# sensor_v5.net
KiCad netlist of a schematic drawn in EAGLE
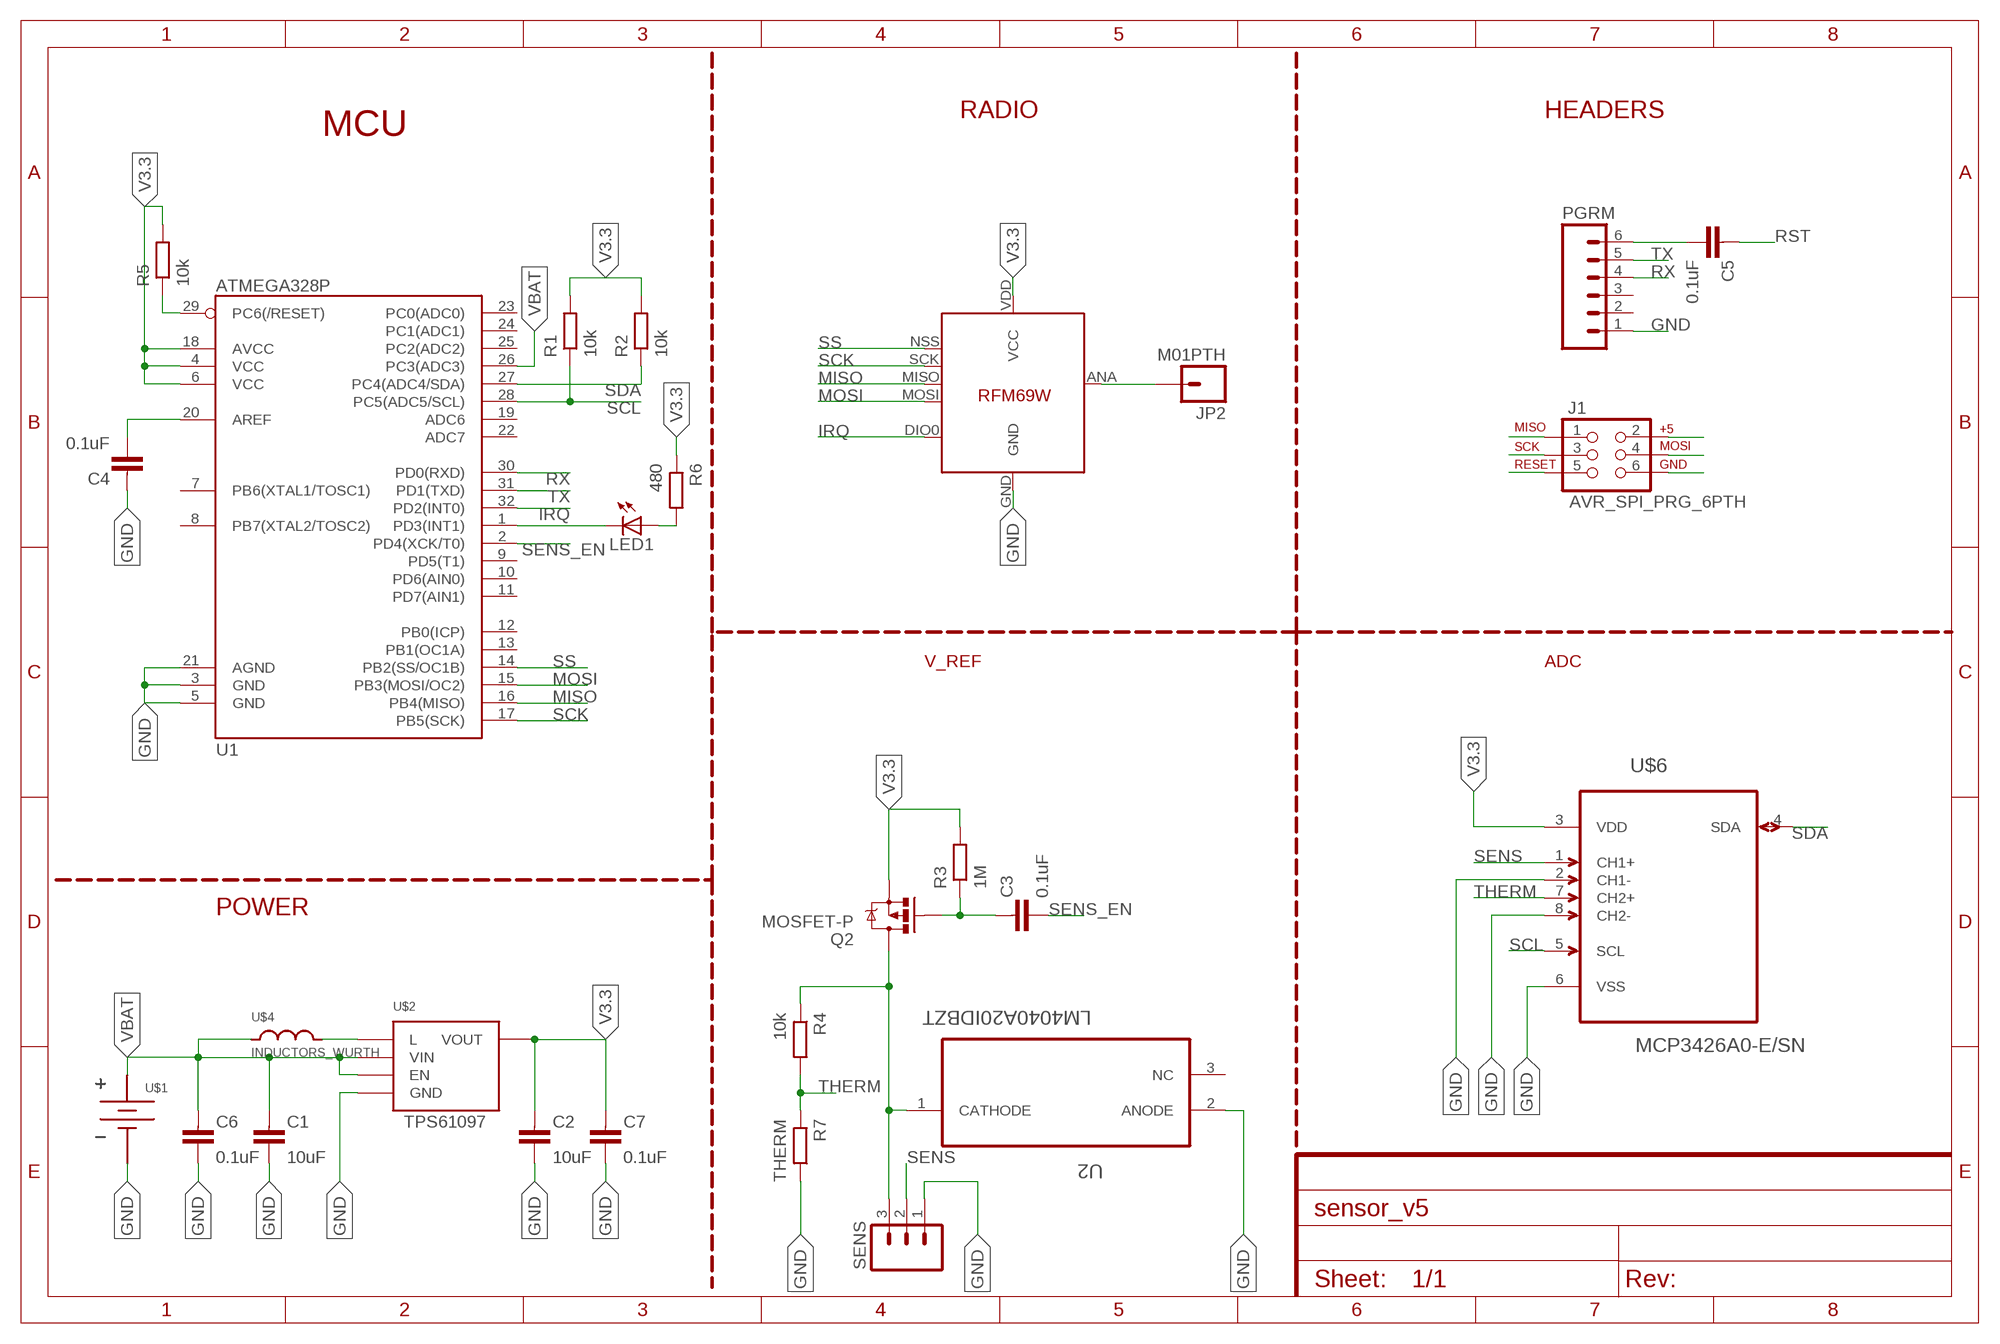
[diagram p0: schematic, sheet 1]

(export (version "E")
  (design (tool "Eeschema 10.0.6"))
  (components
    (comp (ref "C1")
      (value "10uF")
      (footprint "eagle-import:C0805-N")
      (libsource (lib "eagle-import") (part "CAPACITOR0805-N"))
    )
    (comp (ref "C2")
      (value "10uF")
      (footprint "eagle-import:C0805-N")
      (libsource (lib "eagle-import") (part "CAPACITOR0805-N"))
    )
    (comp (ref "C3")
      (value "0.1uF")
      (footprint "eagle-import:C0603-N")
      (libsource (lib "eagle-import") (part "CAPACITOR0603-N"))
    )
    (comp (ref "C4")
      (value "0.1uF")
      (footprint "eagle-import:C0603-N")
      (libsource (lib "eagle-import") (part "CAPACITOR0603-N"))
    )
    (comp (ref "C5")
      (value "0.1uF")
      (footprint "eagle-import:C0603-N")
      (libsource (lib "eagle-import") (part "CAPACITOR0603-N"))
    )
    (comp (ref "C6")
      (value "0.1uF")
      (footprint "eagle-import:C0603-N")
      (libsource (lib "eagle-import") (part "CAPACITOR0603-N"))
    )
    (comp (ref "C7")
      (value "0.1uF")
      (footprint "eagle-import:C0603-N")
      (libsource (lib "eagle-import") (part "CAPACITOR0603-N"))
    )
    (comp (ref "J1")
      (value "AVR_SPI_PRG_6PTH")
      (footprint "eagle-import:2X3")
      (libsource (lib "eagle-import") (part "AVR_SPI_PRG_6PTH"))
    )
    (comp (ref "JP2")
      (value "M01PTH")
      (footprint "eagle-import:1X01")
      (libsource (lib "eagle-import") (part "M01PTH"))
    )
    (comp (ref "LED1")
      (value "LED0603")
      (footprint "eagle-import:LED-0603")
      (libsource (lib "eagle-import") (part "LED0603"))
    )
    (comp (ref "PGRM")
      (value "M06LONGPADS")
      (footprint "eagle-import:1X06_LONGPADS")
      (libsource (lib "eagle-import") (part "M06LONGPADS"))
    )
    (comp (ref "Q2")
      (value "MOSFET-P")
      (footprint "eagle-import:SOT23-3")
      (libsource (lib "eagle-import") (part "MOSFET-PCHANNELIRLML2244"))
    )
    (comp (ref "R1")
      (value "10k")
      (footprint "eagle-import:R0603-N")
      (libsource (lib "eagle-import") (part "RESISTOR0603-N"))
    )
    (comp (ref "R2")
      (value "10k")
      (footprint "eagle-import:R0603-N")
      (libsource (lib "eagle-import") (part "RESISTOR0603-N"))
    )
    (comp (ref "R3")
      (value "1M")
      (footprint "eagle-import:R0603-N")
      (libsource (lib "eagle-import") (part "RESISTOR0603-N"))
    )
    (comp (ref "R4")
      (value "10k")
      (footprint "eagle-import:R0603-N")
      (libsource (lib "eagle-import") (part "RESISTOR0603-N"))
    )
    (comp (ref "R5")
      (value "10k")
      (footprint "eagle-import:R0603-N")
      (libsource (lib "eagle-import") (part "RESISTOR0603-N"))
    )
    (comp (ref "R6")
      (value "480")
      (footprint "eagle-import:R0603-N")
      (libsource (lib "eagle-import") (part "RESISTOR0603-N"))
    )
    (comp (ref "R7")
      (value "THERM")
      (footprint "eagle-import:R0603-N")
      (libsource (lib "eagle-import") (part "RESISTOR0603-N"))
    )
    (comp (ref "SENS")
      (value "M03PTH")
      (footprint "eagle-import:1X03")
      (libsource (lib "eagle-import") (part "M03PTH"))
    )
    (comp (ref "U$1")
      (value "KEYSTONEAAHOLDER_2CELL")
      (footprint "eagle-import:KEYSTONEAAHOLDER_2CELL")
      (libsource (lib "eagle-import") (part "KEYSTONEAAHOLDER_2CELL"))
    )
    (comp (ref "U$2")
      (value "TPS61097-33")
      (footprint "eagle-import:SOT23-5")
      (libsource (lib "eagle-import") (part "TPS61097-33"))
    )
    (comp (ref "U$4")
      (value "INDUCTORS_WURTH")
      (footprint "eagle-import:WURTH_10UH_650MA")
      (libsource (lib "eagle-import") (part "INDUCTORS_WURTH"))
    )
    (comp (ref "U$5")
      (value "RFM69")
      (footprint "eagle-import:RFM69W-MINPADS")
      (libsource (lib "eagle-import") (part "RFM69"))
    )
    (comp (ref "U$6")
      (value "MCP3426A0-E/SN")
      (footprint "eagle-import:SOIC127P600X175-8N")
      (libsource (lib "eagle-import") (part "MCP3426A0-E/SN"))
    )
    (comp (ref "U1")
      (value "ATMEGA328P")
      (footprint "eagle-import:TQFP32-08")
      (libsource (lib "eagle-import") (part "ATMEGA328_SMT"))
    )
    (comp (ref "U2")
      (value "LM4040A20IDBZT")
      (footprint "eagle-import:SOT95P237X112-3N")
      (libsource (lib "eagle-import") (part "LM4040A20IDBZT"))
    )
  )
  (nets
    (net (code "1") (name "/IRQ") (class "Default")
      (node (ref "U$5") (pin "DIO0") (pinfunction "DIO0_DIO0") (pintype "open_collector"))
      (node (ref "U1") (pin "32") (pinfunction "PD2(INT0)_32") (pintype "bidirectional"))
    )
    (net (code "2") (name "/MISO") (class "Default")
      (node (ref "J1") (pin "1") (pinfunction "1_1") (pintype "passive"))
      (node (ref "U$5") (pin "MISO") (pinfunction "MISO_MISO") (pintype "input"))
      (node (ref "U1") (pin "16") (pinfunction "PB4(MISO)_16") (pintype "bidirectional"))
    )
    (net (code "3") (name "/MOSI") (class "Default")
      (node (ref "J1") (pin "4") (pinfunction "4_4") (pintype "passive"))
      (node (ref "U$5") (pin "MOSI") (pinfunction "MOSI_MOSI") (pintype "output"))
      (node (ref "U1") (pin "15") (pinfunction "PB3(MOSI/OC2)_15") (pintype "bidirectional"))
    )
    (net (code "4") (name "/RST") (class "Default")
      (node (ref "C5") (pin "1") (pinfunction "1_1") (pintype "passive"))
      (node (ref "J1") (pin "5") (pinfunction "5_5") (pintype "passive"))
      (node (ref "R5") (pin "1") (pinfunction "P$1_1") (pintype "passive"))
      (node (ref "U1") (pin "29") (pinfunction "PC6(/RESET)_29") (pintype "bidirectional"))
    )
    (net (code "5") (name "/RX") (class "Default")
      (node (ref "PGRM") (pin "4") (pinfunction "4_4") (pintype "passive"))
      (node (ref "U1") (pin "30") (pinfunction "PD0(RXD)_30") (pintype "bidirectional"))
    )
    (net (code "6") (name "/SCK") (class "Default")
      (node (ref "J1") (pin "3") (pinfunction "3_3") (pintype "passive"))
      (node (ref "U$5") (pin "SCK") (pinfunction "SCK_SCK") (pintype "input"))
      (node (ref "U1") (pin "17") (pinfunction "PB5(SCK)_17") (pintype "bidirectional"))
    )
    (net (code "7") (name "/SCL") (class "Default")
      (node (ref "R1") (pin "1") (pinfunction "P$1_1") (pintype "passive"))
      (node (ref "U$6") (pin "5") (pinfunction "SCL_5") (pintype "input"))
      (node (ref "U1") (pin "28") (pinfunction "PC5(ADC5/SCL)_28") (pintype "bidirectional"))
    )
    (net (code "8") (name "/SDA") (class "Default")
      (node (ref "R2") (pin "1") (pinfunction "P$1_1") (pintype "passive"))
      (node (ref "U$6") (pin "4") (pinfunction "SDA_4") (pintype "bidirectional"))
      (node (ref "U1") (pin "27") (pinfunction "PC4(ADC4/SDA)_27") (pintype "bidirectional"))
    )
    (net (code "9") (name "/SENS") (class "Default")
      (node (ref "SENS") (pin "2") (pinfunction "2_2") (pintype "passive"))
      (node (ref "U$6") (pin "1") (pinfunction "CH1+_1") (pintype "input"))
    )
    (net (code "10") (name "/SENS_EN") (class "Default")
      (node (ref "C3") (pin "2") (pinfunction "2_2") (pintype "passive"))
      (node (ref "U1") (pin "2") (pinfunction "PD4(XCK/T0)_2") (pintype "bidirectional"))
    )
    (net (code "11") (name "/SS") (class "Default")
      (node (ref "U$5") (pin "NSS") (pinfunction "SEL_NSS") (pintype "input"))
      (node (ref "U1") (pin "14") (pinfunction "PB2(SS/OC1B)_14") (pintype "bidirectional"))
    )
    (net (code "12") (name "/THERM") (class "Default")
      (node (ref "R4") (pin "2") (pinfunction "P$2_2") (pintype "passive"))
      (node (ref "R7") (pin "1") (pinfunction "P$1_1") (pintype "passive"))
      (node (ref "U$6") (pin "7") (pinfunction "CH2+_7") (pintype "input"))
    )
    (net (code "13") (name "/TX") (class "Default")
      (node (ref "PGRM") (pin "5") (pinfunction "5_5") (pintype "passive"))
      (node (ref "U1") (pin "31") (pinfunction "PD1(TXD)_31") (pintype "bidirectional"))
    )
    (net (code "14") (name "GND") (class "Default")
      (node (ref "C1") (pin "2") (pinfunction "2_2") (pintype "passive"))
      (node (ref "C2") (pin "2") (pinfunction "2_2") (pintype "passive"))
      (node (ref "C4") (pin "1") (pinfunction "1_1") (pintype "passive"))
      (node (ref "C6") (pin "2") (pinfunction "2_2") (pintype "passive"))
      (node (ref "C7") (pin "2") (pinfunction "2_2") (pintype "passive"))
      (node (ref "J1") (pin "6") (pinfunction "6_6") (pintype "passive"))
      (node (ref "PGRM") (pin "1") (pinfunction "1_1") (pintype "passive"))
      (node (ref "R7") (pin "2") (pinfunction "P$2_2") (pintype "passive"))
      (node (ref "SENS") (pin "1") (pinfunction "1_1") (pintype "passive"))
      (node (ref "U$1") (pin "P$2") (pinfunction "GND_P$2") (pintype "bidirectional"))
      (node (ref "U$2") (pin "P$2") (pinfunction "GND_P$2") (pintype "power_in"))
      (node (ref "U$5") (pin "GND") (pinfunction "GND_GND") (pintype "power_in"))
      (node (ref "U$6") (pin "2") (pinfunction "CH1-_2") (pintype "input"))
      (node (ref "U$6") (pin "6") (pinfunction "VSS_6") (pintype "power_in"))
      (node (ref "U$6") (pin "8") (pinfunction "CH2-_8") (pintype "input"))
      (node (ref "U1") (pin "21") (pinfunction "AGND_21") (pintype "bidirectional"))
      (node (ref "U1") (pin "3") (pinfunction "GND_3") (pintype "bidirectional"))
      (node (ref "U1") (pin "5") (pinfunction "GND_5") (pintype "bidirectional"))
      (node (ref "U2") (pin "2") (pinfunction "ANODE_2") (pintype "input"))
    )
    (net (code "15") (name "Net-(C5-Pad2)") (class "Default")
      (node (ref "C5") (pin "2") (pinfunction "2_2") (pintype "passive"))
      (node (ref "PGRM") (pin "6") (pinfunction "6_6") (pintype "passive"))
    )
    (net (code "16") (name "Net-(Q2-D)") (class "Default")
      (node (ref "Q2") (pin "3") (pinfunction "D_3") (pintype "passive"))
      (node (ref "R4") (pin "1") (pinfunction "P$1_1") (pintype "passive"))
      (node (ref "SENS") (pin "3") (pinfunction "3_3") (pintype "passive"))
      (node (ref "U2") (pin "1") (pinfunction "CATHODE_1") (pintype "output"))
    )
    (net (code "17") (name "Net-(Q2-G)") (class "Default")
      (node (ref "C3") (pin "1") (pinfunction "1_1") (pintype "passive"))
      (node (ref "Q2") (pin "1") (pinfunction "G_1") (pintype "passive"))
      (node (ref "R3") (pin "1") (pinfunction "P$1_1") (pintype "passive"))
    )
    (net (code "18") (name "Net-(R6-P$2)") (class "Default")
      (node (ref "LED1") (pin "A") (pinfunction "A_A") (pintype "passive"))
      (node (ref "R6") (pin "2") (pinfunction "P$2_2") (pintype "passive"))
    )
    (net (code "19") (name "Net-(U$2-L)") (class "Default")
      (node (ref "U$2") (pin "P$5") (pinfunction "L_P$5") (pintype "bidirectional"))
      (node (ref "U$4") (pin "P$1") (pinfunction "P$1_P$1") (pintype "passive"))
    )
    (net (code "20") (name "Net-(U$5-ANT)") (class "Default")
      (node (ref "JP2") (pin "1") (pinfunction "1_1") (pintype "passive"))
      (node (ref "U$5") (pin "ANA") (pinfunction "ANT_ANA") (pintype "passive"))
    )
    (net (code "21") (name "Net-(U1-AREF)") (class "Default")
      (node (ref "C4") (pin "2") (pinfunction "2_2") (pintype "passive"))
      (node (ref "U1") (pin "20") (pinfunction "AREF_20") (pintype "bidirectional"))
    )
    (net (code "22") (name "Net-(U1-PD3(INT1))") (class "Default")
      (node (ref "LED1") (pin "C") (pinfunction "C_C") (pintype "passive"))
      (node (ref "U1") (pin "1") (pinfunction "PD3(INT1)_1") (pintype "bidirectional"))
    )
    (net (code "23") (name "V3.3") (class "Default")
      (node (ref "C2") (pin "1") (pinfunction "1_1") (pintype "passive"))
      (node (ref "C7") (pin "1") (pinfunction "1_1") (pintype "passive"))
      (node (ref "J1") (pin "2") (pinfunction "2_2") (pintype "passive"))
      (node (ref "Q2") (pin "2") (pinfunction "S_2") (pintype "passive"))
      (node (ref "R1") (pin "2") (pinfunction "P$2_2") (pintype "passive"))
      (node (ref "R2") (pin "2") (pinfunction "P$2_2") (pintype "passive"))
      (node (ref "R3") (pin "2") (pinfunction "P$2_2") (pintype "passive"))
      (node (ref "R5") (pin "2") (pinfunction "P$2_2") (pintype "passive"))
      (node (ref "R6") (pin "1") (pinfunction "P$1_1") (pintype "passive"))
      (node (ref "U$2") (pin "P$4") (pinfunction "VOUT_P$4") (pintype "power_in"))
      (node (ref "U$5") (pin "VDD") (pinfunction "VCC_VDD") (pintype "power_in"))
      (node (ref "U$6") (pin "3") (pinfunction "VDD_3") (pintype "power_in"))
      (node (ref "U1") (pin "18") (pinfunction "AVCC_18") (pintype "bidirectional"))
      (node (ref "U1") (pin "4") (pinfunction "VCC_4") (pintype "bidirectional"))
      (node (ref "U1") (pin "6") (pinfunction "VCC_6") (pintype "bidirectional"))
    )
    (net (code "24") (name "VBAT") (class "Default")
      (node (ref "C1") (pin "1") (pinfunction "1_1") (pintype "passive"))
      (node (ref "C6") (pin "1") (pinfunction "1_1") (pintype "passive"))
      (node (ref "U$1") (pin "P$1") (pinfunction "VBAT_P$1") (pintype "bidirectional"))
      (node (ref "U$2") (pin "P$1") (pinfunction "VIN_P$1") (pintype "power_in"))
      (node (ref "U$2") (pin "P$3") (pinfunction "EN_P$3") (pintype "bidirectional"))
      (node (ref "U$4") (pin "P$2") (pinfunction "P$2_P$2") (pintype "passive"))
      (node (ref "U1") (pin "26") (pinfunction "PC3(ADC3)_26") (pintype "bidirectional"))
    )
    (net (code "25") (name "unconnected-(PGRM-Pad2)") (class "Default")
      (node (ref "PGRM") (pin "2") (pinfunction "2_2") (pintype "passive"))
    )
    (net (code "26") (name "unconnected-(PGRM-Pad3)") (class "Default")
      (node (ref "PGRM") (pin "3") (pinfunction "3_3") (pintype "passive"))
    )
    (net (code "27") (name "unconnected-(U1-ADC6-Pad19)") (class "Default")
      (node (ref "U1") (pin "19") (pinfunction "ADC6_19") (pintype "bidirectional"))
    )
    (net (code "28") (name "unconnected-(U1-ADC7-Pad22)") (class "Default")
      (node (ref "U1") (pin "22") (pinfunction "ADC7_22") (pintype "bidirectional"))
    )
    (net (code "29") (name "unconnected-(U1-PB0(ICP)-Pad12)") (class "Default")
      (node (ref "U1") (pin "12") (pinfunction "PB0(ICP)_12") (pintype "bidirectional"))
    )
    (net (code "30") (name "unconnected-(U1-PB1(OC1A)-Pad13)") (class "Default")
      (node (ref "U1") (pin "13") (pinfunction "PB1(OC1A)_13") (pintype "bidirectional"))
    )
    (net (code "31") (name "unconnected-(U1-PB6(XTAL1{slash}TOSC1)-Pad7)") (class "Default")
      (node (ref "U1") (pin "7") (pinfunction "PB6(XTAL1/TOSC1)_7") (pintype "bidirectional"))
    )
    (net (code "32") (name "unconnected-(U1-PB7(XTAL2{slash}TOSC2)-Pad8)") (class "Default")
      (node (ref "U1") (pin "8") (pinfunction "PB7(XTAL2/TOSC2)_8") (pintype "bidirectional"))
    )
    (net (code "33") (name "unconnected-(U1-PC0(ADC0)-Pad23)") (class "Default")
      (node (ref "U1") (pin "23") (pinfunction "PC0(ADC0)_23") (pintype "bidirectional"))
    )
    (net (code "34") (name "unconnected-(U1-PC1(ADC1)-Pad24)") (class "Default")
      (node (ref "U1") (pin "24") (pinfunction "PC1(ADC1)_24") (pintype "bidirectional"))
    )
    (net (code "35") (name "unconnected-(U1-PC2(ADC2)-Pad25)") (class "Default")
      (node (ref "U1") (pin "25") (pinfunction "PC2(ADC2)_25") (pintype "bidirectional"))
    )
    (net (code "36") (name "unconnected-(U1-PD5(T1)-Pad9)") (class "Default")
      (node (ref "U1") (pin "9") (pinfunction "PD5(T1)_9") (pintype "bidirectional"))
    )
    (net (code "37") (name "unconnected-(U1-PD6(AIN0)-Pad10)") (class "Default")
      (node (ref "U1") (pin "10") (pinfunction "PD6(AIN0)_10") (pintype "bidirectional"))
    )
    (net (code "38") (name "unconnected-(U1-PD7(AIN1)-Pad11)") (class "Default")
      (node (ref "U1") (pin "11") (pinfunction "PD7(AIN1)_11") (pintype "bidirectional"))
    )
    (net (code "39") (name "unconnected-(U2-NC-Pad3)") (class "Default")
      (node (ref "U2") (pin "3") (pinfunction "NC_3") (pintype "no_connect"))
    )
  )
)
